# Sheet1.net
KiCad netlist of a schematic drawn in Altium Designer
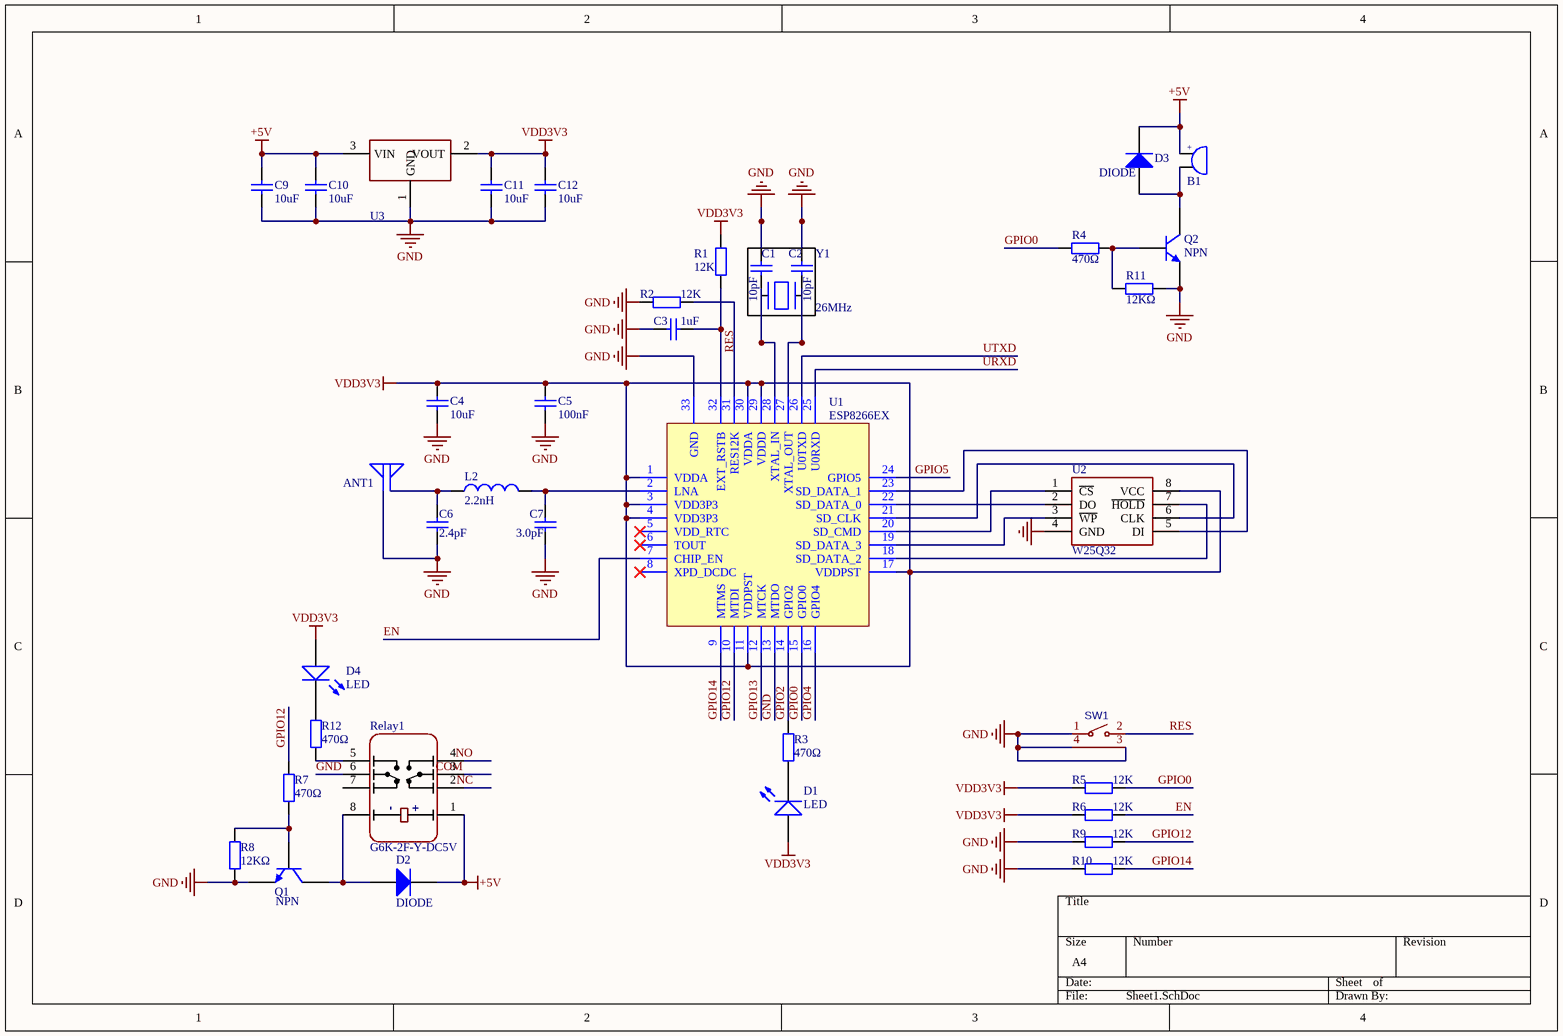
[diagram p0: Sheet1.SchDoc]

(export (version "E")
  (design (tool "Eeschema 10.0.6"))
  (components
    (comp (ref "ANT1")
      (value "ANT")
      (footprint "ESP8266-WiiFi-ANT")
      (description "WiFi天线")
      (libsource (lib "SchLibrary") (part "ANT"))
    )
    (comp (ref "B1")
      (value "BEEP")
      (footprint "BUZZER-5020")
      (description "蜂鸣器")
      (fields (field (name "版权归属") "源创客"))
      (libsource (lib "SchLibrary") (part "BEEP"))
    )
    (comp (ref "C1")
      (value "10pF")
      (footprint "0402C")
      (description "贴片电容")
      (libsource (lib "Altium Designer封装库") (part "CAP"))
    )
    (comp (ref "C2")
      (value "10pF")
      (footprint "0402C")
      (description "贴片电容")
      (libsource (lib "Altium Designer封装库") (part "CAP"))
    )
    (comp (ref "C3")
      (value "1uF")
      (footprint "0402C")
      (description "贴片电容")
      (libsource (lib "Miscellaneous Devices LC") (part "0402 100nF (104) 10% 16V"))
    )
    (comp (ref "C4")
      (value "10uF")
      (footprint "0603C")
      (description "贴片电容")
      (libsource (lib "Miscellaneous Devices LC") (part "0603 100nF (104) 10% 50V"))
    )
    (comp (ref "C5")
      (value "100nF")
      (footprint "0603C")
      (description "贴片电容")
      (libsource (lib "Miscellaneous Devices LC") (part "0402 100nF (104) 10% 16V"))
    )
    (comp (ref "C6")
      (value "2.4pF")
      (footprint "0402C")
      (description "贴片电容")
      (libsource (lib "Altium Designer封装库") (part "CAP"))
    )
    (comp (ref "C7")
      (value "3.0pF")
      (footprint "0402C")
      (description "贴片电容")
      (libsource (lib "Altium Designer封装库") (part "CAP"))
    )
    (comp (ref "C9")
      (value "10uF")
      (footprint "0603C")
      (description "贴片电容")
      (libsource (lib "Miscellaneous Devices LC") (part "0603 100nF (104) 10% 50V"))
    )
    (comp (ref "C10")
      (value "10uF")
      (footprint "0603C")
      (description "贴片电容")
      (libsource (lib "Miscellaneous Devices LC") (part "0603 100nF (104) 10% 50V"))
    )
    (comp (ref "C11")
      (value "10uF")
      (footprint "0603C")
      (description "贴片电容")
      (libsource (lib "Miscellaneous Devices LC") (part "0603 100nF (104) 10% 50V"))
    )
    (comp (ref "C12")
      (value "10uF")
      (footprint "0603C")
      (description "贴片电容")
      (libsource (lib "Miscellaneous Devices LC") (part "0603 100nF (104) 10% 50V"))
    )
    (comp (ref "D1")
      (value "LED")
      (footprint "0603LED")
      (description "发光二极管")
      (libsource (lib "SchLibrary") (part "LED"))
    )
    (comp (ref "D2")
      (value "DIODE")
      (footprint "DIODE-SOD-323")
      (description "二极管")
      (libsource (lib "SchLibrary") (part "DIODE"))
    )
    (comp (ref "D3")
      (value "DIODE")
      (footprint "DIODE-SOD-323")
      (description "二极管")
      (libsource (lib "SchLibrary") (part "DIODE"))
    )
    (comp (ref "D4")
      (value "LED")
      (footprint "0603LED")
      (description "发光二极管")
      (libsource (lib "SchLibrary") (part "LED"))
    )
    (comp (ref "L2")
      (value "2.2nH")
      (footprint "0402L")
      (description "电感")
      (libsource (lib "SchLibrary") (part "INDUCTOR"))
    )
    (comp (ref "Q1")
      (value "NPN")
      (footprint "SOT-23-3")
      (description "三极管")
      (libsource (lib "SchLibrary") (part "NPN"))
    )
    (comp (ref "Q2")
      (value "NPN")
      (footprint "SOT-23-3")
      (description "三极管")
      (libsource (lib "SchLibrary") (part "NPN"))
    )
    (comp (ref "R1")
      (value "12K")
      (footprint "0402R")
      (description "贴片电阻")
      (libsource (lib "") (part "0402 1.2KΩ (1201) 1%_1"))
    )
    (comp (ref "R2")
      (value "12K")
      (footprint "0402R")
      (description "贴片电阻")
      (libsource (lib "Miscellaneous Devices LC") (part "0402 1.2KΩ (1201) 1%"))
    )
    (comp (ref "R3")
      (value "470Ω")
      (footprint "0402R")
      (description "贴片电阻")
      (libsource (lib "") (part "0402 1.2KΩ (1201) 1%_2"))
    )
    (comp (ref "R4")
      (value "470Ω")
      (footprint "0402R")
      (description "贴片电阻")
      (libsource (lib "") (part "0402 1.2KΩ (1201) 1%_3"))
    )
    (comp (ref "R5")
      (value "12K")
      (footprint "0402R")
      (description "贴片电阻")
      (libsource (lib "Miscellaneous Devices LC") (part "0402 1.2KΩ (1201) 1%"))
    )
    (comp (ref "R6")
      (value "12K")
      (footprint "0402R")
      (description "贴片电阻")
      (libsource (lib "Miscellaneous Devices LC") (part "0402 1.2KΩ (1201) 1%"))
    )
    (comp (ref "R7")
      (value "470Ω")
      (footprint "0402R")
      (description "贴片电阻")
      (libsource (lib "") (part "0402 1.2KΩ (1201) 1%_2"))
    )
    (comp (ref "R8")
      (value "12KΩ")
      (footprint "0402R")
      (description "贴片电阻")
      (libsource (lib "") (part "0402 1.2KΩ (1201) 1%_2"))
    )
    (comp (ref "R9")
      (value "12K")
      (footprint "0402R")
      (description "贴片电阻")
      (libsource (lib "Miscellaneous Devices LC") (part "0402 1.2KΩ (1201) 1%"))
    )
    (comp (ref "R10")
      (value "12K")
      (footprint "0402R")
      (description "贴片电阻")
      (libsource (lib "Miscellaneous Devices LC") (part "0402 1.2KΩ (1201) 1%"))
    )
    (comp (ref "R11")
      (value "12KΩ")
      (footprint "0402R")
      (description "贴片电阻")
      (libsource (lib "") (part "0402 1.2KΩ (1201) 1%_3"))
    )
    (comp (ref "R12")
      (value "470Ω")
      (footprint "0402R")
      (description "贴片电阻")
      (libsource (lib "") (part "0402 1.2KΩ (1201) 1%_1"))
    )
    (comp (ref "Relay1")
      (value "G6K-2F-Y-DC5V")
      (footprint "RELAY-G6K-2F-Y")
      (description "欧娒龙超小型信号继电器")
      (libsource (lib "SchLibrary") (part "G6K-2F-Y-DC5V"))
    )
    (comp (ref "SW1")
      (value "SWITCH_4P_SIDE_PRESS")
      (footprint "SWITCH_SMD_2P_SIDE_PRESS")
      (description "侧边轻触按键")
      (libsource (lib "SchLibrary") (part "SWITCH_4P_SIDE_PRESS"))
    )
    (comp (ref "U1")
      (value "ESP8266EX")
      (footprint "QFN-32-ESP8266EX")
      (description "WiFi芯片")
      (libsource (lib "Schlib1") (part "ESP8266EX"))
    )
    (comp (ref "U2")
      (value "W25Q32")
      (footprint "SOIC-8")
      (description "SPI Flash")
      (libsource (lib "SchLibrary") (part "W25Q32"))
    )
    (comp (ref "U3")
      (value "AMS1117")
      (footprint "SOT-89-3")
      (description "LDO降压芯片")
      (libsource (lib "SchLibrary") (part "AMS1117"))
    )
    (comp (ref "Y1")
      (value "26MHz")
      (footprint "SMD-3225-4Pin")
      (description "贴片晶振")
      (libsource (lib "Altium Designer封装库") (part "CRYSTAL"))
    )
  )
  (nets
    (net (code "1") (name "+5V") (class "Default")
      (node (ref "B1") (pin "1") (pinfunction "1_1") (pintype "passive"))
      (node (ref "C10") (pin "2") (pinfunction "2_2") (pintype "passive"))
      (node (ref "C9") (pin "2") (pinfunction "2_2") (pintype "passive"))
      (node (ref "D2") (pin "2") (pinfunction "K_2") (pintype "passive"))
      (node (ref "D3") (pin "2") (pinfunction "K_2") (pintype "passive"))
      (node (ref "Relay1") (pin "1") (pinfunction "+_1") (pintype "passive"))
      (node (ref "U3") (pin "3") (pinfunction "VIN_3") (pintype "passive"))
    )
    (net (code "2") (name "/COM") (class "Default")
      (node (ref "Relay1") (pin "3") (pinfunction "COM_3") (pintype "passive"))
    )
    (net (code "3") (name "/EN") (class "Default")
      (node (ref "R6") (pin "1") (pinfunction "1_1") (pintype "passive"))
      (node (ref "U1") (pin "7") (pinfunction "CHIP_EN_7") (pintype "passive"))
    )
    (net (code "4") (name "/GPIO0") (class "Default")
      (node (ref "R4") (pin "1") (pinfunction "1_1") (pintype "passive"))
      (node (ref "R5") (pin "1") (pinfunction "1_1") (pintype "passive"))
      (node (ref "U1") (pin "15") (pinfunction "GPIO0_15") (pintype "passive"))
    )
    (net (code "5") (name "/GPIO2") (class "Default")
      (node (ref "R3") (pin "1") (pinfunction "1_1") (pintype "passive"))
      (node (ref "U1") (pin "14") (pinfunction "GPIO2_14") (pintype "passive"))
    )
    (net (code "6") (name "/GPIO4") (class "Default")
      (node (ref "U1") (pin "16") (pinfunction "GPIO4_16") (pintype "passive"))
    )
    (net (code "7") (name "/GPIO5") (class "Default")
      (node (ref "U1") (pin "24") (pinfunction "GPIO5_24") (pintype "passive"))
    )
    (net (code "8") (name "/GPIO12") (class "Default")
      (node (ref "R7") (pin "1") (pinfunction "1_1") (pintype "passive"))
      (node (ref "R9") (pin "1") (pinfunction "1_1") (pintype "passive"))
      (node (ref "U1") (pin "10") (pinfunction "MTDI_10") (pintype "passive"))
    )
    (net (code "9") (name "/GPIO13") (class "Default")
      (node (ref "U1") (pin "12") (pinfunction "MTCK_12") (pintype "passive"))
    )
    (net (code "10") (name "/GPIO14") (class "Default")
      (node (ref "R10") (pin "1") (pinfunction "1_1") (pintype "passive"))
      (node (ref "U1") (pin "9") (pinfunction "MTMS_9") (pintype "passive"))
    )
    (net (code "11") (name "/NC") (class "Default")
      (node (ref "Relay1") (pin "2") (pinfunction "NC_2") (pintype "passive"))
    )
    (net (code "12") (name "/NO") (class "Default")
      (node (ref "Relay1") (pin "4") (pinfunction "NO_4") (pintype "passive"))
    )
    (net (code "13") (name "/RES") (class "Default")
      (node (ref "C3") (pin "1") (pinfunction "1_1") (pintype "passive"))
      (node (ref "R1") (pin "1") (pinfunction "1_1") (pintype "passive"))
      (node (ref "SW1") (pin "2") (pinfunction "2_2") (pintype "passive"))
      (node (ref "U1") (pin "32") (pinfunction "EXT_RSTB_32") (pintype "passive"))
    )
    (net (code "14") (name "/URXD") (class "Default")
      (node (ref "U1") (pin "25") (pinfunction "U0RXD_25") (pintype "passive"))
    )
    (net (code "15") (name "/UTXD") (class "Default")
      (node (ref "U1") (pin "26") (pinfunction "U0TXD_26") (pintype "passive"))
    )
    (net (code "16") (name "GND") (class "Default")
      (node (ref "ANT1") (pin "1") (pinfunction "GND_1") (pintype "passive"))
      (node (ref "C1") (pin "2") (pinfunction "2_2") (pintype "passive"))
      (node (ref "C10") (pin "1") (pinfunction "1_1") (pintype "passive"))
      (node (ref "C11") (pin "1") (pinfunction "1_1") (pintype "passive"))
      (node (ref "C12") (pin "1") (pinfunction "1_1") (pintype "passive"))
      (node (ref "C2") (pin "2") (pinfunction "2_2") (pintype "passive"))
      (node (ref "C3") (pin "2") (pinfunction "2_2") (pintype "passive"))
      (node (ref "C4") (pin "1") (pinfunction "1_1") (pintype "passive"))
      (node (ref "C5") (pin "2") (pinfunction "2_2") (pintype "passive"))
      (node (ref "C6") (pin "2") (pinfunction "2_2") (pintype "passive"))
      (node (ref "C7") (pin "2") (pinfunction "2_2") (pintype "passive"))
      (node (ref "C9") (pin "1") (pinfunction "1_1") (pintype "passive"))
      (node (ref "Q1") (pin "2") (pinfunction "E_2") (pintype "passive"))
      (node (ref "Q2") (pin "2") (pinfunction "E_2") (pintype "passive"))
      (node (ref "R10") (pin "2") (pinfunction "2_2") (pintype "passive"))
      (node (ref "R11") (pin "2") (pinfunction "2_2") (pintype "passive"))
      (node (ref "R2") (pin "2") (pinfunction "2_2") (pintype "passive"))
      (node (ref "R8") (pin "2") (pinfunction "2_2") (pintype "passive"))
      (node (ref "R9") (pin "2") (pinfunction "2_2") (pintype "passive"))
      (node (ref "Relay1") (pin "6") (pinfunction "NO_6") (pintype "passive"))
      (node (ref "SW1") (pin "1") (pinfunction "1_1") (pintype "passive"))
      (node (ref "SW1") (pin "3") (pinfunction "3_3") (pintype "passive"))
      (node (ref "SW1") (pin "4") (pinfunction "4_4") (pintype "passive"))
      (node (ref "U1") (pin "13") (pinfunction "MTDO_13") (pintype "passive"))
      (node (ref "U1") (pin "33") (pinfunction "GND_33") (pintype "passive"))
      (node (ref "U2") (pin "4") (pinfunction "GND_4") (pintype "passive"))
      (node (ref "U3") (pin "1") (pinfunction "GND_1") (pintype "passive"))
      (node (ref "Y1") (pin "2") (pinfunction "G_2") (pintype "passive"))
      (node (ref "Y1") (pin "4") (pinfunction "G_4") (pintype "passive"))
    )
    (net (code "17") (name "Net-(ANT1-ANT)") (class "Default")
      (node (ref "ANT1") (pin "2") (pinfunction "ANT_2") (pintype "passive"))
      (node (ref "C6") (pin "1") (pinfunction "1_1") (pintype "passive"))
      (node (ref "L2") (pin "1") (pinfunction "1_1") (pintype "passive"))
    )
    (net (code "18") (name "Net-(D1-Pad2)") (class "Default")
      (node (ref "D1") (pin "2") (pinfunction "2_2") (pintype "passive"))
      (node (ref "R3") (pin "2") (pinfunction "2_2") (pintype "passive"))
    )
    (net (code "19") (name "Net-(D2-A)") (class "Default")
      (node (ref "D2") (pin "1") (pinfunction "A_1") (pintype "passive"))
      (node (ref "Q1") (pin "3") (pinfunction "C_3") (pintype "passive"))
      (node (ref "Relay1") (pin "8") (pinfunction "-_8") (pintype "passive"))
    )
    (net (code "20") (name "Net-(D3-A)") (class "Default")
      (node (ref "B1") (pin "2") (pinfunction "2_2") (pintype "passive"))
      (node (ref "D3") (pin "1") (pinfunction "A_1") (pintype "passive"))
      (node (ref "Q2") (pin "3") (pinfunction "C_3") (pintype "passive"))
    )
    (net (code "21") (name "Net-(D4-Pad2)") (class "Default")
      (node (ref "D4") (pin "2") (pinfunction "2_2") (pintype "passive"))
      (node (ref "R12") (pin "2") (pinfunction "2_2") (pintype "passive"))
    )
    (net (code "22") (name "Net-(Q1-B)") (class "Default")
      (node (ref "Q1") (pin "1") (pinfunction "B_1") (pintype "passive"))
      (node (ref "R7") (pin "2") (pinfunction "2_2") (pintype "passive"))
      (node (ref "R8") (pin "1") (pinfunction "1_1") (pintype "passive"))
    )
    (net (code "23") (name "Net-(Q2-B)") (class "Default")
      (node (ref "Q2") (pin "1") (pinfunction "B_1") (pintype "passive"))
      (node (ref "R11") (pin "1") (pinfunction "1_1") (pintype "passive"))
      (node (ref "R4") (pin "2") (pinfunction "2_2") (pintype "passive"))
    )
    (net (code "24") (name "Net-(R12-Pad1)") (class "Default")
      (node (ref "R12") (pin "1") (pinfunction "1_1") (pintype "passive"))
      (node (ref "Relay1") (pin "5") (pinfunction "NO_5") (pintype "passive"))
    )
    (net (code "25") (name "Net-(U1-LNA)") (class "Default")
      (node (ref "C7") (pin "1") (pinfunction "1_1") (pintype "passive"))
      (node (ref "L2") (pin "2") (pinfunction "2_2") (pintype "passive"))
      (node (ref "U1") (pin "2") (pinfunction "LNA_2") (pintype "passive"))
    )
    (net (code "26") (name "Net-(U1-RES12K)") (class "Default")
      (node (ref "R2") (pin "1") (pinfunction "1_1") (pintype "passive"))
      (node (ref "U1") (pin "31") (pinfunction "RES12K_31") (pintype "passive"))
    )
    (net (code "27") (name "Net-(U1-SD_CLK)") (class "Default")
      (node (ref "U1") (pin "21") (pinfunction "SD_CLK_21") (pintype "passive"))
      (node (ref "U2") (pin "6") (pinfunction "CLK_6") (pintype "passive"))
    )
    (net (code "28") (name "Net-(U1-SD_CMD)") (class "Default")
      (node (ref "U1") (pin "20") (pinfunction "SD_CMD_20") (pintype "passive"))
      (node (ref "U2") (pin "1") (pinfunction "~{CS}_1") (pintype "passive"))
    )
    (net (code "29") (name "Net-(U1-SD_DATA_0)") (class "Default")
      (node (ref "U1") (pin "22") (pinfunction "SD_DATA_0_22") (pintype "passive"))
      (node (ref "U2") (pin "2") (pinfunction "DO_2") (pintype "passive"))
    )
    (net (code "30") (name "Net-(U1-SD_DATA_1)") (class "Default")
      (node (ref "U1") (pin "23") (pinfunction "SD_DATA_1_23") (pintype "passive"))
      (node (ref "U2") (pin "5") (pinfunction "DI_5") (pintype "passive"))
    )
    (net (code "31") (name "Net-(U1-SD_DATA_2)") (class "Default")
      (node (ref "U1") (pin "18") (pinfunction "SD_DATA_2_18") (pintype "passive"))
      (node (ref "U2") (pin "7") (pinfunction "~{HOLD}_7") (pintype "passive"))
    )
    (net (code "32") (name "Net-(U1-SD_DATA_3)") (class "Default")
      (node (ref "U1") (pin "19") (pinfunction "SD_DATA_3_19") (pintype "passive"))
      (node (ref "U2") (pin "3") (pinfunction "~{WP}_3") (pintype "passive"))
    )
    (net (code "33") (name "Net-(U1-XTAL_IN)") (class "Default")
      (node (ref "C1") (pin "1") (pinfunction "1_1") (pintype "passive"))
      (node (ref "U1") (pin "28") (pinfunction "XTAL_IN_28") (pintype "passive"))
      (node (ref "Y1") (pin "1") (pinfunction "I_1") (pintype "passive"))
    )
    (net (code "34") (name "Net-(U1-XTAL_OUT)") (class "Default")
      (node (ref "C2") (pin "1") (pinfunction "1_1") (pintype "passive"))
      (node (ref "U1") (pin "27") (pinfunction "XTAL_OUT_27") (pintype "passive"))
      (node (ref "Y1") (pin "3") (pinfunction "O_3") (pintype "passive"))
    )
    (net (code "35") (name "VDD3V3") (class "Default")
      (node (ref "C11") (pin "2") (pinfunction "2_2") (pintype "passive"))
      (node (ref "C12") (pin "2") (pinfunction "2_2") (pintype "passive"))
      (node (ref "C4") (pin "2") (pinfunction "2_2") (pintype "passive"))
      (node (ref "C5") (pin "1") (pinfunction "1_1") (pintype "passive"))
      (node (ref "D1") (pin "1") (pinfunction "1_1") (pintype "passive"))
      (node (ref "D4") (pin "1") (pinfunction "1_1") (pintype "passive"))
      (node (ref "R1") (pin "2") (pinfunction "2_2") (pintype "passive"))
      (node (ref "R5") (pin "2") (pinfunction "2_2") (pintype "passive"))
      (node (ref "R6") (pin "2") (pinfunction "2_2") (pintype "passive"))
      (node (ref "U1") (pin "1") (pinfunction "VDDA_1") (pintype "passive"))
      (node (ref "U1") (pin "11") (pinfunction "VDDPST_11") (pintype "passive"))
      (node (ref "U1") (pin "17") (pinfunction "VDDPST_17") (pintype "passive"))
      (node (ref "U1") (pin "29") (pinfunction "VDDD_29") (pintype "passive"))
      (node (ref "U1") (pin "3") (pinfunction "VDD3P3_3") (pintype "passive"))
      (node (ref "U1") (pin "30") (pinfunction "VDDA_30") (pintype "passive"))
      (node (ref "U1") (pin "4") (pinfunction "VDD3P3_4") (pintype "passive"))
      (node (ref "U2") (pin "8") (pinfunction "VCC_8") (pintype "passive"))
      (node (ref "U3") (pin "2") (pinfunction "VOUT_2") (pintype "passive"))
    )
    (net (code "36") (name "unconnected-(Relay1-NC-Pad7)") (class "Default")
      (node (ref "Relay1") (pin "7") (pinfunction "NC_7") (pintype "passive"))
    )
    (net (code "37") (name "unconnected-(U1-TOUT-Pad6)") (class "Default")
      (node (ref "U1") (pin "6") (pinfunction "TOUT_6") (pintype "passive+no_connect"))
    )
    (net (code "38") (name "unconnected-(U1-VDD_RTC-Pad5)") (class "Default")
      (node (ref "U1") (pin "5") (pinfunction "VDD_RTC_5") (pintype "passive+no_connect"))
    )
    (net (code "39") (name "unconnected-(U1-XPD_DCDC-Pad8)") (class "Default")
      (node (ref "U1") (pin "8") (pinfunction "XPD_DCDC_8") (pintype "passive+no_connect"))
    )
  )
)
